# sensor_specific.net
KiCad netlist of a schematic drawn in Altium Designer
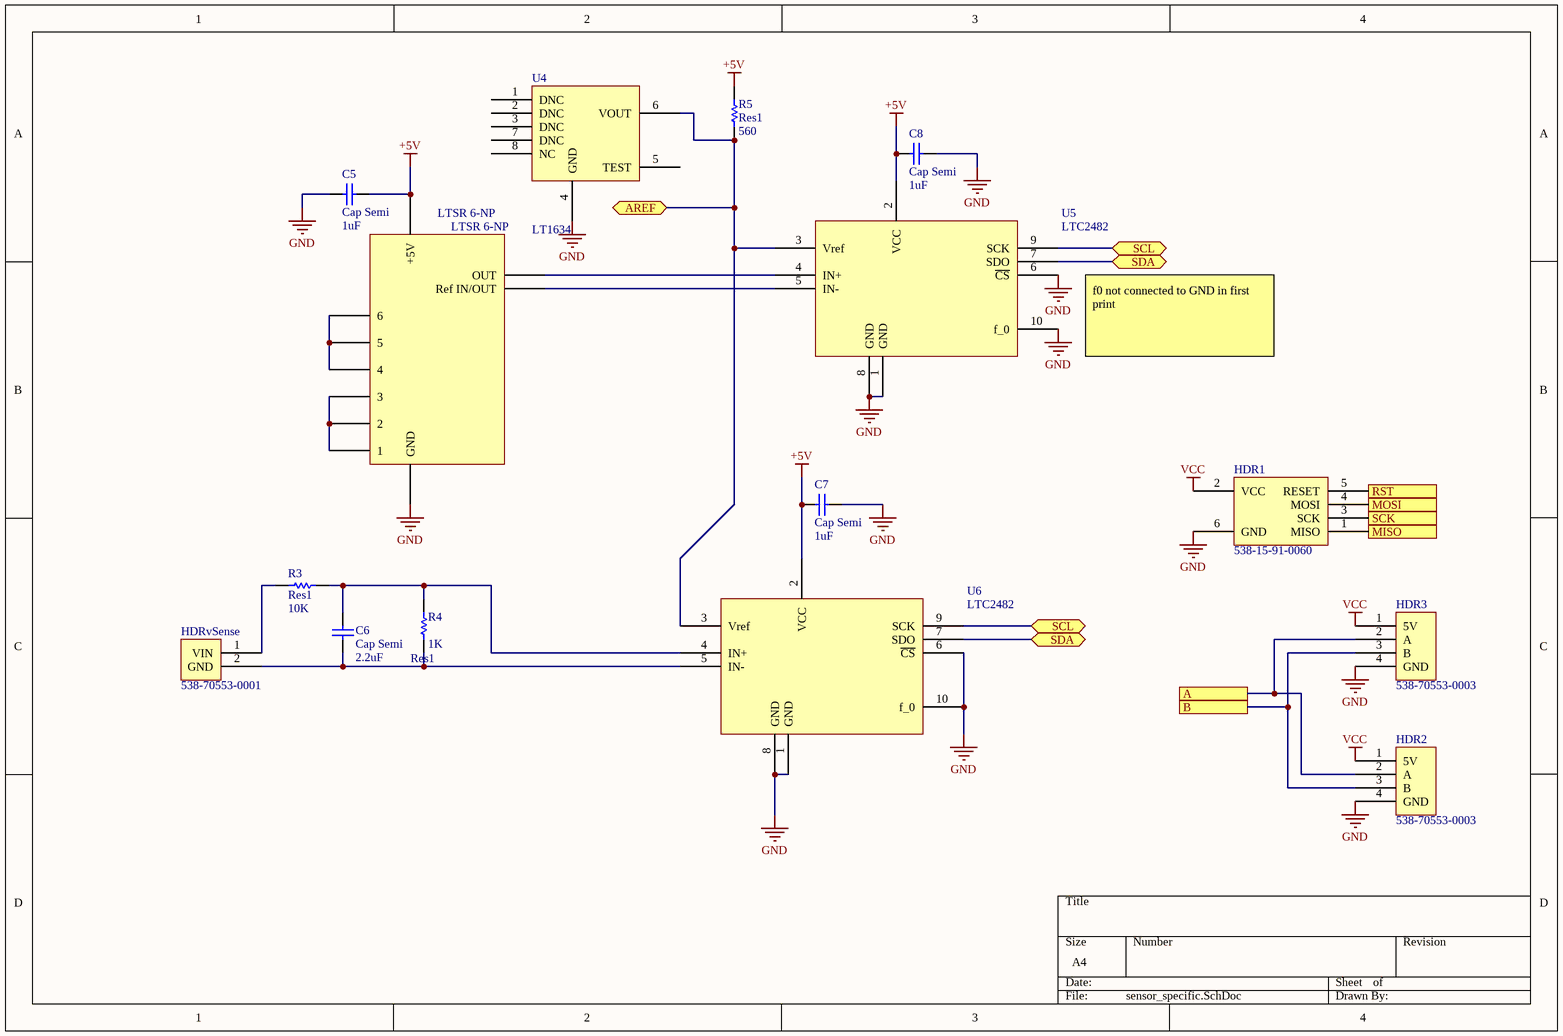
[diagram p0: sensor_specific.SchDoc]

(export (version "E")
  (design (tool "Eeschema 10.0.6"))
  (components
    (comp (ref "C5")
      (value "Cap Semi")
      (footprint "1608[0603]")
      (description "Capacitor (Semiconductor SIM Model)")
      (fields (field (name "ALTIUM_VALUE") "1uF") (field (name "PUBLISHER") "Altium Limited"))
      (libsource (lib "Miscellaneous Devices") (part "Cap Semi"))
    )
    (comp (ref "C6")
      (value "Cap Semi")
      (footprint "1608[0603]")
      (description "Capacitor (Semiconductor SIM Model)")
      (fields (field (name "ALTIUM_VALUE") "2.2uF") (field (name "PUBLISHER") "Altium Limited"))
      (libsource (lib "Miscellaneous Devices") (part "Cap Semi"))
    )
    (comp (ref "C7")
      (value "Cap Semi")
      (footprint "1608[0603]")
      (description "Capacitor (Semiconductor SIM Model)")
      (fields (field (name "ALTIUM_VALUE") "1uF") (field (name "PUBLISHER") "Altium Limited"))
      (libsource (lib "Miscellaneous Devices") (part "Cap Semi"))
    )
    (comp (ref "C8")
      (value "Cap Semi")
      (footprint "1608[0603]")
      (description "Capacitor (Semiconductor SIM Model)")
      (fields (field (name "ALTIUM_VALUE") "1uF") (field (name "PUBLISHER") "Altium Limited"))
      (libsource (lib "Miscellaneous Devices") (part "Cap Semi"))
    )
    (comp (ref "HDR1")
      (value "Programming header")
      (footprint "MOLEX_HEADER_6_SMD")
      (fields (field (name "SUPPLIER PART NUMBER 1") "538-15-91-0060"))
      (libsource (lib "Integrated_Library") (part "PRGM_HDR"))
    )
    (comp (ref "HDR2")
      (value "RS-485 interface")
      (footprint "MOLEX_HEADER_4H_SHRD")
      (description "Part Number: 70553-0003. MABSS connector")
      (fields (field (name "SUPPLIER PART NUMBER 1") "538-70553-0003"))
      (libsource (lib "Integrated_Library") (part "MABSS_RS485"))
    )
    (comp (ref "HDR3")
      (value "RS-485 interface")
      (footprint "MOLEX_HEADER_4H_SHRD")
      (description "Part Number: 70553-0003. MABSS connector")
      (fields (field (name "SUPPLIER PART NUMBER 1") "538-70553-0003"))
      (libsource (lib "Integrated_Library") (part "MABSS_RS485"))
    )
    (comp (ref "HDRvSense")
      (value "MOLEX_HEADER_2H_SHRD")
      (footprint "MOLEX_HEADER_2H_SHRD")
      (description "Part Number: 70553-0001. 2-wire signal inputs")
      (fields (field (name "SUPPLIER PART NUMBER 1") "538-70553-0001"))
      (libsource (lib "Integrated_Library") (part "MOLEX_HEADER_2H_SHRD"))
    )
    (comp (ref "LTSR 6-NP")
      (value "LTSR 6-NP")
      (footprint "LTSR 6-NP")
      (libsource (lib "MABSS") (part "LTSR 6-NP"))
    )
    (comp (ref "R3")
      (value "Res1")
      (footprint "6-0805_N")
      (description "Resistor")
      (fields (field (name "ALTIUM_VALUE") "10K") (field (name "PUBLISHER") "Altium Limited"))
      (libsource (lib "Miscellaneous Devices") (part "Res1"))
    )
    (comp (ref "R4")
      (value "Res1")
      (footprint "6-0805_N")
      (description "Resistor")
      (fields (field (name "ALTIUM_VALUE") "1K") (field (name "PUBLISHER") "Altium Limited"))
      (libsource (lib "Miscellaneous Devices") (part "Res1"))
    )
    (comp (ref "R5")
      (value "Res1")
      (footprint "6-0805_N")
      (description "Resistor")
      (fields (field (name "ALTIUM_VALUE") "560") (field (name "PUBLISHER") "Altium Limited"))
      (libsource (lib "Miscellaneous Devices") (part "Res1"))
    )
    (comp (ref "U4") (value "LT1634") (footprint "8S1_N") (libsource (lib "MABSS") (part "LT1634")))
    (comp (ref "U5") (value "LTC2482") (footprint "DFN33") (libsource (lib "MABSS") (part "LTC2482")))
    (comp (ref "U6") (value "LTC2482") (footprint "DFN33") (libsource (lib "MABSS") (part "LTC2482")))
  )
  (nets
    (net (code "1") (name "+5V") (class "Default")
      (node (ref "C5") (pin "2") (pinfunction "2_2") (pintype "passive"))
      (node (ref "C7") (pin "1") (pinfunction "1_1") (pintype "passive"))
      (node (ref "C8") (pin "1") (pinfunction "1_1") (pintype "passive"))
      (node (ref "LTSR 6-NP") (pin "+5V") (pinfunction "+5V_+5V") (pintype "passive"))
      (node (ref "R5") (pin "2") (pinfunction "2_2") (pintype "passive"))
      (node (ref "U5") (pin "2") (pinfunction "VCC_2") (pintype "passive"))
      (node (ref "U6") (pin "2") (pinfunction "VCC_2") (pintype "passive"))
    )
    (net (code "2") (name "/A") (class "Default")
      (node (ref "HDR2") (pin "2") (pinfunction "A_2") (pintype "passive"))
      (node (ref "HDR3") (pin "2") (pinfunction "A_2") (pintype "passive"))
    )
    (net (code "3") (name "/AREF") (class "Default")
      (node (ref "R5") (pin "1") (pinfunction "1_1") (pintype "passive"))
      (node (ref "U4") (pin "6") (pinfunction "VOUT_6") (pintype "passive"))
      (node (ref "U5") (pin "3") (pinfunction "Vref_3") (pintype "passive"))
      (node (ref "U6") (pin "3") (pinfunction "Vref_3") (pintype "passive"))
    )
    (net (code "4") (name "/B") (class "Default")
      (node (ref "HDR2") (pin "3") (pinfunction "B_3") (pintype "passive"))
      (node (ref "HDR3") (pin "3") (pinfunction "B_3") (pintype "passive"))
    )
    (net (code "5") (name "/MISO") (class "Default")
      (node (ref "HDR1") (pin "1") (pinfunction "MISO_1") (pintype "passive"))
    )
    (net (code "6") (name "/MOSI") (class "Default")
      (node (ref "HDR1") (pin "4") (pinfunction "MOSI_4") (pintype "passive"))
    )
    (net (code "7") (name "/RST") (class "Default")
      (node (ref "HDR1") (pin "5") (pinfunction "RESET_5") (pintype "passive"))
    )
    (net (code "8") (name "/SCK") (class "Default")
      (node (ref "HDR1") (pin "3") (pinfunction "SCK_3") (pintype "passive"))
    )
    (net (code "9") (name "/SCL") (class "Default")
      (node (ref "U5") (pin "9") (pinfunction "SCK_9") (pintype "passive"))
      (node (ref "U6") (pin "9") (pinfunction "SCK_9") (pintype "passive"))
    )
    (net (code "10") (name "/SDA") (class "Default")
      (node (ref "U5") (pin "7") (pinfunction "SDO_7") (pintype "passive"))
      (node (ref "U6") (pin "7") (pinfunction "SDO_7") (pintype "passive"))
    )
    (net (code "11") (name "GND") (class "Default")
      (node (ref "C5") (pin "1") (pinfunction "1_1") (pintype "passive"))
      (node (ref "C7") (pin "2") (pinfunction "2_2") (pintype "passive"))
      (node (ref "C8") (pin "2") (pinfunction "2_2") (pintype "passive"))
      (node (ref "HDR1") (pin "6") (pinfunction "GND_6") (pintype "passive"))
      (node (ref "HDR2") (pin "4") (pinfunction "GND_4") (pintype "passive"))
      (node (ref "HDR3") (pin "4") (pinfunction "GND_4") (pintype "passive"))
      (node (ref "LTSR 6-NP") (pin "GND") (pinfunction "GND_GND") (pintype "passive"))
      (node (ref "U4") (pin "4") (pinfunction "GND_4") (pintype "passive"))
      (node (ref "U5") (pin "1") (pinfunction "GND_1") (pintype "passive"))
      (node (ref "U5") (pin "10") (pinfunction "f_0_10") (pintype "passive"))
      (node (ref "U5") (pin "6") (pinfunction "~{CS}_6") (pintype "passive"))
      (node (ref "U5") (pin "8") (pinfunction "GND_8") (pintype "passive"))
      (node (ref "U6") (pin "1") (pinfunction "GND_1") (pintype "passive"))
      (node (ref "U6") (pin "10") (pinfunction "f_0_10") (pintype "passive"))
      (node (ref "U6") (pin "6") (pinfunction "~{CS}_6") (pintype "passive"))
      (node (ref "U6") (pin "8") (pinfunction "GND_8") (pintype "passive"))
    )
    (net (code "12") (name "Net-(HDRvSense-GND)") (class "Default")
      (node (ref "C6") (pin "1") (pinfunction "1_1") (pintype "passive"))
      (node (ref "HDRvSense") (pin "2") (pinfunction "GND_2") (pintype "passive"))
      (node (ref "R4") (pin "2") (pinfunction "2_2") (pintype "passive"))
      (node (ref "U6") (pin "5") (pinfunction "IN-_5") (pintype "passive"))
    )
    (net (code "13") (name "Net-(HDRvSense-VIN)") (class "Default")
      (node (ref "HDRvSense") (pin "1") (pinfunction "VIN_1") (pintype "passive"))
      (node (ref "R3") (pin "2") (pinfunction "2_2") (pintype "passive"))
    )
    (net (code "14") (name "Net-(LTSR 6-NP-Pad1)") (class "Default")
      (node (ref "LTSR 6-NP") (pin "1") (pinfunction "1_1") (pintype "passive"))
      (node (ref "LTSR 6-NP") (pin "2") (pinfunction "2_2") (pintype "passive"))
      (node (ref "LTSR 6-NP") (pin "3") (pinfunction "3_3") (pintype "passive"))
    )
    (net (code "15") (name "Net-(LTSR 6-NP-Pad4)") (class "Default")
      (node (ref "LTSR 6-NP") (pin "4") (pinfunction "4_4") (pintype "passive"))
      (node (ref "LTSR 6-NP") (pin "5") (pinfunction "5_5") (pintype "passive"))
      (node (ref "LTSR 6-NP") (pin "6") (pinfunction "6_6") (pintype "passive"))
    )
    (net (code "16") (name "Net-(LTSR 6-NP-Ref_IN{slash}OUT)") (class "Default")
      (node (ref "LTSR 6-NP") (pin "ref") (pinfunction "Ref_IN/OUT_ref") (pintype "passive"))
      (node (ref "U5") (pin "5") (pinfunction "IN-_5") (pintype "passive"))
    )
    (net (code "17") (name "Net-(U5-IN+)") (class "Default")
      (node (ref "LTSR 6-NP") (pin "OUT") (pinfunction "OUT_OUT") (pintype "passive"))
      (node (ref "U5") (pin "4") (pinfunction "IN+_4") (pintype "passive"))
    )
    (net (code "18") (name "Net-(U6-IN+)") (class "Default")
      (node (ref "C6") (pin "2") (pinfunction "2_2") (pintype "passive"))
      (node (ref "R3") (pin "1") (pinfunction "1_1") (pintype "passive"))
      (node (ref "R4") (pin "1") (pinfunction "1_1") (pintype "passive"))
      (node (ref "U6") (pin "4") (pinfunction "IN+_4") (pintype "passive"))
    )
    (net (code "19") (name "VCC") (class "Default")
      (node (ref "HDR1") (pin "2") (pinfunction "VCC_2") (pintype "passive"))
      (node (ref "HDR2") (pin "1") (pinfunction "5V_1") (pintype "passive"))
      (node (ref "HDR3") (pin "1") (pinfunction "5V_1") (pintype "passive"))
    )
    (net (code "20") (name "unconnected-(U4-DNC-Pad1)") (class "Default")
      (node (ref "U4") (pin "1") (pinfunction "DNC_1") (pintype "passive"))
    )
    (net (code "21") (name "unconnected-(U4-DNC-Pad2)") (class "Default")
      (node (ref "U4") (pin "2") (pinfunction "DNC_2") (pintype "passive"))
    )
    (net (code "22") (name "unconnected-(U4-DNC-Pad3)") (class "Default")
      (node (ref "U4") (pin "3") (pinfunction "DNC_3") (pintype "passive"))
    )
    (net (code "23") (name "unconnected-(U4-DNC-Pad7)") (class "Default")
      (node (ref "U4") (pin "7") (pinfunction "DNC_7") (pintype "passive"))
    )
    (net (code "24") (name "unconnected-(U4-NC-Pad8)") (class "Default")
      (node (ref "U4") (pin "8") (pinfunction "NC_8") (pintype "passive"))
    )
    (net (code "25") (name "unconnected-(U4-TEST-Pad5)") (class "Default")
      (node (ref "U4") (pin "5") (pinfunction "TEST_5") (pintype "passive"))
    )
  )
)
